# TOBD_STM32.net
KiCad netlist of a schematic drawn in EAGLE
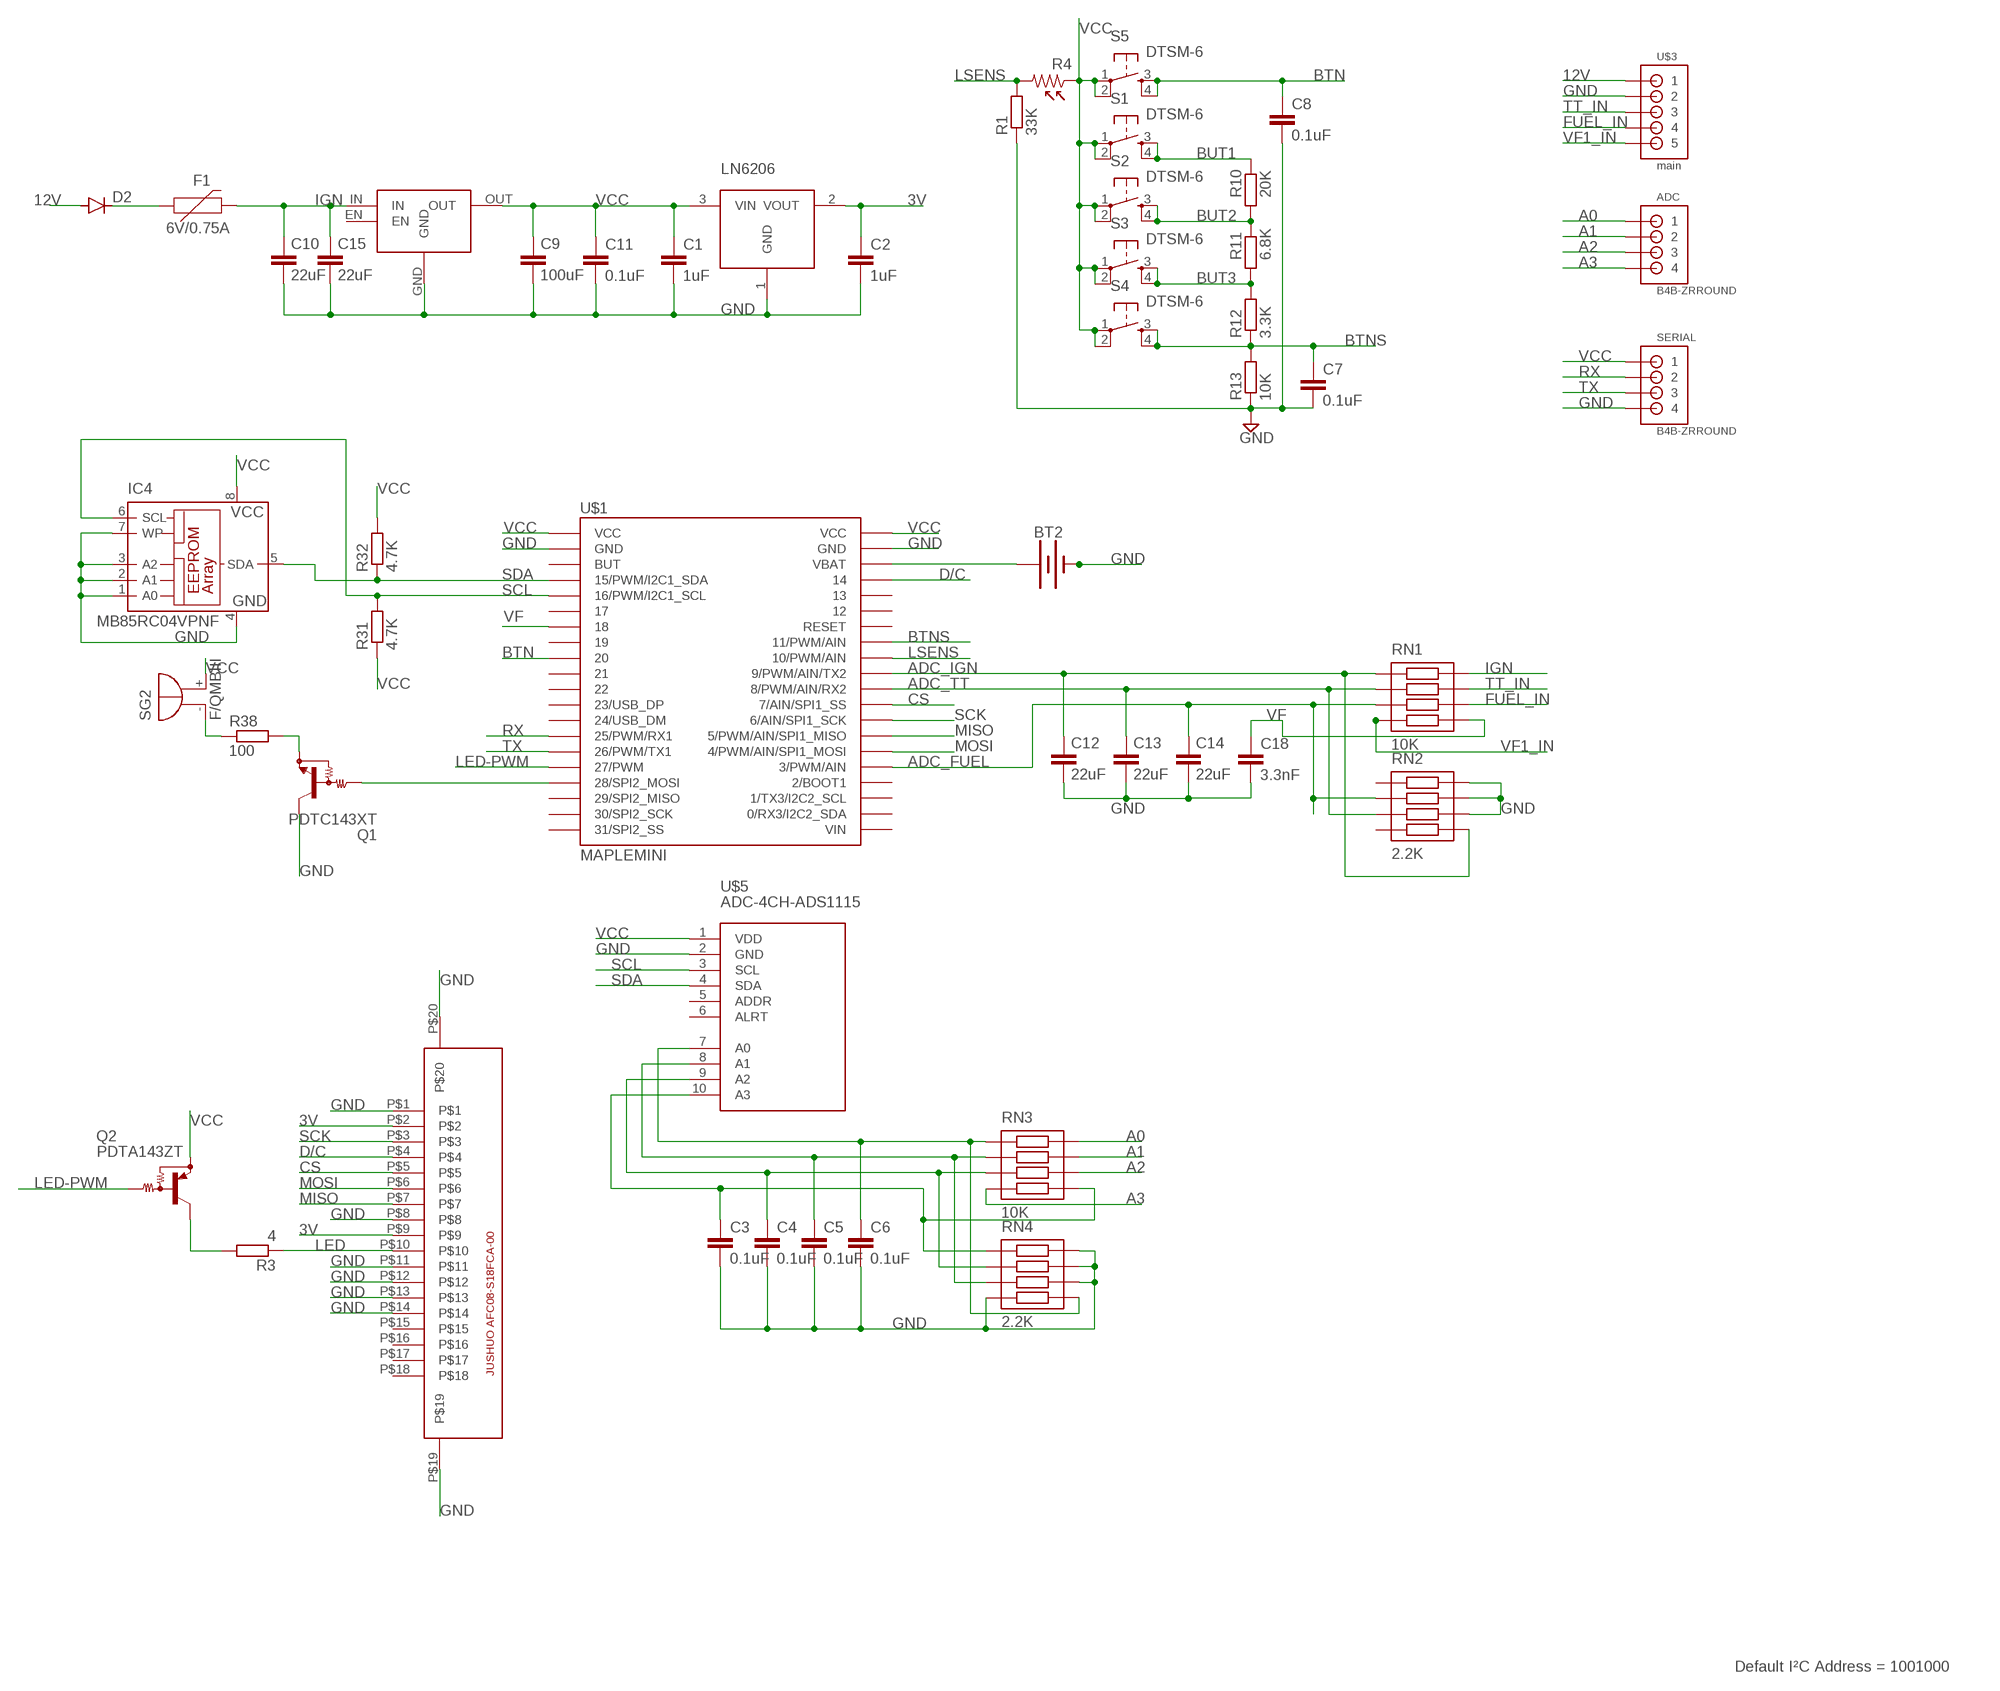
[diagram p0: schematic, sheet 1]

(export (version "E")
  (design (tool "Eeschema 10.0.6"))
  (components
    (comp (ref "ADC")
      (value "B4B-ZRROUND")
      (footprint "eagle-import:B4B-ZR")
      (libsource (lib "eagle-import") (part "B4B-ZRROUND"))
    )
    (comp (ref "BT2")
      (value "BATTERY")
      (footprint "eagle-import:BATTCOM_20MM_VERTICAL")
      (libsource (lib "eagle-import") (part "BATTERY"))
    )
    (comp (ref "C1")
      (value "1uF")
      (footprint "eagle-import:C0805")
      (fields (field (name "MF") "Samsung Electro-Mechanics") (field (name "MPN") "CL21F105ZOFNNNE"))
      (libsource (lib "eagle-import") (part "C-EUC0805"))
    )
    (comp (ref "C2")
      (value "1uF")
      (footprint "eagle-import:C0805")
      (fields (field (name "MF") "Samsung Electro-Mechanics") (field (name "MPN") "CL21F105ZOFNNNE"))
      (libsource (lib "eagle-import") (part "C-EUC0805"))
    )
    (comp (ref "C3")
      (value "0.1uF")
      (footprint "eagle-import:C0805")
      (fields (field (name "MF") "Samsung Electro-Mechanics") (field (name "MPN") "CL21F104ZBCNNNC"))
      (libsource (lib "eagle-import") (part "C-EUC0805"))
    )
    (comp (ref "C4")
      (value "0.1uF")
      (footprint "eagle-import:C0805")
      (fields (field (name "MF") "Samsung Electro-Mechanics") (field (name "MPN") "CL21F104ZBCNNNC"))
      (libsource (lib "eagle-import") (part "C-EUC0805"))
    )
    (comp (ref "C5")
      (value "0.1uF")
      (footprint "eagle-import:C0805")
      (fields (field (name "MF") "Samsung Electro-Mechanics") (field (name "MPN") "CL21F104ZBCNNNC"))
      (libsource (lib "eagle-import") (part "C-EUC0805"))
    )
    (comp (ref "C6")
      (value "0.1uF")
      (footprint "eagle-import:C0805")
      (fields (field (name "MF") "Samsung Electro-Mechanics") (field (name "MPN") "CL21F104ZBCNNNC"))
      (libsource (lib "eagle-import") (part "C-EUC0805"))
    )
    (comp (ref "C7")
      (value "0.1uF")
      (footprint "eagle-import:C0805")
      (fields (field (name "MF") "Samsung Electro-Mechanics") (field (name "MPN") "CL21F104ZBCNNNC"))
      (libsource (lib "eagle-import") (part "C-EUC0805"))
    )
    (comp (ref "C8")
      (value "0.1uF")
      (footprint "eagle-import:C0805")
      (fields (field (name "MF") "Samsung Electro-Mechanics") (field (name "MPN") "CL21F104ZBCNNNC"))
      (libsource (lib "eagle-import") (part "C-EUC0805"))
    )
    (comp (ref "C9")
      (value "100uF")
      (footprint "eagle-import:C1210K")
      (fields (field (name "MF") "Murata Electronics") (field (name "MPN") "GRM32ER60J107ME20L"))
      (libsource (lib "eagle-import") (part "resistor_348_C-EUC1210K"))
    )
    (comp (ref "C10")
      (value "22uF")
      (footprint "eagle-import:C0805")
      (fields (field (name "MF") "Samsung Electro-Mechanics") (field (name "MPN") "CL21A226MAQNNNE"))
      (libsource (lib "eagle-import") (part "resistor_348_C-EUC0805"))
    )
    (comp (ref "C11")
      (value "0.1uF")
      (footprint "eagle-import:C0805")
      (fields (field (name "MF") "Samsung Electro-Mechanics") (field (name "MPN") "CL21F104ZBCNNNC"))
      (libsource (lib "eagle-import") (part "C-EUC0805"))
    )
    (comp (ref "C12")
      (value "22uF")
      (footprint "eagle-import:C0805")
      (fields (field (name "MF") "Samsung Electro-Mechanics") (field (name "MPN") "CL21A226MAQNNNE"))
      (libsource (lib "eagle-import") (part "resistor_348_C-EUC0805"))
    )
    (comp (ref "C13")
      (value "22uF")
      (footprint "eagle-import:C0805")
      (fields (field (name "MF") "Samsung Electro-Mechanics") (field (name "MPN") "CL21A226MAQNNNE"))
      (libsource (lib "eagle-import") (part "resistor_348_C-EUC0805"))
    )
    (comp (ref "C14")
      (value "22uF")
      (footprint "eagle-import:C0805")
      (fields (field (name "MF") "Samsung Electro-Mechanics") (field (name "MPN") "CL21A226MAQNNNE"))
      (libsource (lib "eagle-import") (part "resistor_348_C-EUC0805"))
    )
    (comp (ref "C15")
      (value "22uF")
      (footprint "eagle-import:C0805")
      (fields (field (name "MF") "Samsung Electro-Mechanics") (field (name "MPN") "CL21A226MAQNNNE"))
      (libsource (lib "eagle-import") (part "resistor_348_C-EUC0805"))
    )
    (comp (ref "C18")
      (value "3.3nF")
      (footprint "eagle-import:C0805")
      (fields (field (name "MPN") "CL21B332KBANNNC"))
      (libsource (lib "eagle-import") (part "C-EUC0805"))
    )
    (comp (ref "D2")
      (value "DIODE-DO-214AC")
      (footprint "eagle-import:DO-214AC")
      (libsource (lib "eagle-import") (part "DIODE-DO-214AC"))
    )
    (comp (ref "F1")
      (value "6V/0.75A")
      (footprint "eagle-import:1206")
      (libsource (lib "eagle-import") (part "PPTC_THREE-QUARTER-AMP"))
    )
    (comp (ref "IC4")
      (value "MB85RC04VPNF")
      (footprint "eagle-import:SO-08")
      (libsource (lib "eagle-import") (part "24CSN04A"))
    )
    (comp (ref "LN6206")
      (value "MCP1700")
      (footprint "eagle-import:SOT23")
      (fields (field (name "MPN") "LN6206P302MR-G"))
      (libsource (lib "eagle-import") (part "MCP1700"))
    )
    (comp (ref "Q1")
      (value "PDTC143XT")
      (footprint "eagle-import:SC59-BEC")
      (libsource (lib "eagle-import") (part "MUN2211T1"))
    )
    (comp (ref "Q2")
      (value "PDTA143ZT")
      (footprint "eagle-import:SC59-BEC")
      (libsource (lib "eagle-import") (part "MUN2111T1"))
    )
    (comp (ref "R1")
      (value "33K")
      (footprint "eagle-import:R0805")
      (libsource (lib "eagle-import") (part "R-EU_R0805"))
    )
    (comp (ref "R3")
      (value "4")
      (footprint "eagle-import:R0805")
      (libsource (lib "eagle-import") (part "R-EU_R0805"))
    )
    (comp (ref "R4")
      (value "PHOTORESPDV-P9")
      (footprint "eagle-import:PDV-P9XXX")
      (libsource (lib "eagle-import") (part "PHOTORESPDV-P9"))
    )
    (comp (ref "R10")
      (value "20K")
      (footprint "eagle-import:R0805")
      (libsource (lib "eagle-import") (part "R-EU_R0805"))
    )
    (comp (ref "R11")
      (value "6.8K")
      (footprint "eagle-import:R0805")
      (libsource (lib "eagle-import") (part "R-EU_R0805"))
    )
    (comp (ref "R12")
      (value "3.3K")
      (footprint "eagle-import:R0805")
      (libsource (lib "eagle-import") (part "R-EU_R0805"))
    )
    (comp (ref "R13")
      (value "10K")
      (footprint "eagle-import:R0805")
      (libsource (lib "eagle-import") (part "R-EU_R0805"))
    )
    (comp (ref "R31")
      (value "4.7K")
      (footprint "eagle-import:R0805")
      (libsource (lib "eagle-import") (part "R-EU_R0805"))
    )
    (comp (ref "R32")
      (value "4.7K")
      (footprint "eagle-import:R0805")
      (libsource (lib "eagle-import") (part "R-EU_R0805"))
    )
    (comp (ref "R38")
      (value "100")
      (footprint "eagle-import:R0805")
      (libsource (lib "eagle-import") (part "R-EU_R0805"))
    )
    (comp (ref "RN1")
      (value "10K")
      (footprint "eagle-import:CTS-744_083")
      (fields (field (name "MPN") "CRA064RJ10K0E04Z"))
      (libsource (lib "eagle-import") (part "RN2_EU-4"))
    )
    (comp (ref "RN2")
      (value "2.2K")
      (footprint "eagle-import:CTS-744_083")
      (fields (field (name "MPN") "CRA064RJ10K0E04Z"))
      (libsource (lib "eagle-import") (part "RN2_EU-4"))
    )
    (comp (ref "RN3")
      (value "10K")
      (footprint "eagle-import:CTS-744_083")
      (fields (field (name "MPN") "CRA064RJ10K0E04Z"))
      (libsource (lib "eagle-import") (part "RN2_EU-4"))
    )
    (comp (ref "RN4")
      (value "2.2K")
      (footprint "eagle-import:CTS-744_083")
      (fields (field (name "MPN") "CRA064RJ10K0E04Z"))
      (libsource (lib "eagle-import") (part "RN2_EU-4"))
    )
    (comp (ref "S1")
      (value "DTSM-6")
      (footprint "eagle-import:DTSM-6")
      (libsource (lib "eagle-import") (part "DTSM-6"))
    )
    (comp (ref "S2")
      (value "DTSM-6")
      (footprint "eagle-import:DTSM-6")
      (libsource (lib "eagle-import") (part "DTSM-6"))
    )
    (comp (ref "S3")
      (value "DTSM-6")
      (footprint "eagle-import:DTSM-6")
      (libsource (lib "eagle-import") (part "DTSM-6"))
    )
    (comp (ref "S4")
      (value "DTSM-6")
      (footprint "eagle-import:DTSM-6")
      (libsource (lib "eagle-import") (part "DTSM-6"))
    )
    (comp (ref "S5")
      (value "DTSM-6")
      (footprint "eagle-import:DTSM-6")
      (libsource (lib "eagle-import") (part "DTSM-6"))
    )
    (comp (ref "SERIAL")
      (value "B4B-ZRROUND")
      (footprint "eagle-import:B4B-ZR")
      (libsource (lib "eagle-import") (part "B4B-ZRROUND"))
    )
    (comp (ref "SG2")
      (value "F/QMBIII")
      (footprint "eagle-import:F_QMBIII")
      (libsource (lib "eagle-import") (part "F/QMBIII"))
    )
    (comp (ref "U$1")
      (value "MAPLEMINI")
      (footprint "eagle-import:20-DIP")
      (libsource (lib "eagle-import") (part "MAPLEMINI"))
    )
    (comp (ref "U$2")
      (value "JUSHUOAFC08-S18FCA-00")
      (footprint "eagle-import:JUSHUOAFC08-S18FCA-00")
      (fields (field (name "MPN") "AFC08-S18FCA-00"))
      (libsource (lib "eagle-import") (part "JUSHUOAFC08-S18FCA-00"))
    )
    (comp (ref "U$3")
      (value "main")
      (footprint "eagle-import:B5B-ZR-LONG")
      (libsource (lib "eagle-import") (part "B5B-ZRLONG"))
    )
    (comp (ref "U$4")
      (value "MINI-DC-DC-3AV")
      (footprint "eagle-import:MINI-DC-DC-3AV")
      (libsource (lib "eagle-import") (part "MINI-DC-DC-3AV"))
    )
    (comp (ref "U$5")
      (value "ADC-4CH-ADS1115")
      (footprint "eagle-import:ADC-4CH-ADS1115")
      (libsource (lib "eagle-import") (part "ADC-4CH-ADS1115"))
    )
  )
  (nets
    (net (code "1") (name "/3V") (class "Default")
      (node (ref "C2") (pin "1") (pinfunction "1_1") (pintype "passive"))
      (node (ref "LN6206") (pin "2") (pinfunction "VOUT_2") (pintype "bidirectional"))
      (node (ref "U$2") (pin "P$2") (pinfunction "P$2_P$2") (pintype "bidirectional"))
      (node (ref "U$2") (pin "P$9") (pinfunction "P$9_P$9") (pintype "bidirectional"))
    )
    (net (code "2") (name "/12V") (class "Default")
      (node (ref "D2") (pin "A") (pinfunction "A_A") (pintype "passive"))
      (node (ref "U$3") (pin "1") (pinfunction "1_1") (pintype "bidirectional"))
    )
    (net (code "3") (name "/A0") (class "Default")
      (node (ref "ADC") (pin "1") (pinfunction "1_1") (pintype "bidirectional"))
      (node (ref "RN3") (pin "5") (pinfunction "8_5") (pintype "passive"))
    )
    (net (code "4") (name "/A1") (class "Default")
      (node (ref "ADC") (pin "2") (pinfunction "2_2") (pintype "bidirectional"))
      (node (ref "RN3") (pin "6") (pinfunction "7_6") (pintype "passive"))
    )
    (net (code "5") (name "/A2") (class "Default")
      (node (ref "ADC") (pin "3") (pinfunction "3_3") (pintype "bidirectional"))
      (node (ref "RN3") (pin "7") (pinfunction "6_7") (pintype "passive"))
    )
    (net (code "6") (name "/A3") (class "Default")
      (node (ref "ADC") (pin "4") (pinfunction "4_4") (pintype "bidirectional"))
      (node (ref "RN3") (pin "8") (pinfunction "4_8") (pintype "passive"))
    )
    (net (code "7") (name "/ADC_FUEL") (class "Default")
      (node (ref "C14") (pin "1") (pinfunction "1_1") (pintype "passive"))
      (node (ref "RN1") (pin "2") (pinfunction "3_2") (pintype "passive"))
      (node (ref "RN2") (pin "3") (pinfunction "2_3") (pintype "passive"))
      (node (ref "U$1") (pin "25") (pinfunction "3/PWM/AIN_25") (pintype "bidirectional"))
    )
    (net (code "8") (name "/ADC_IGN") (class "Default")
      (node (ref "C12") (pin "1") (pinfunction "1_1") (pintype "passive"))
      (node (ref "RN1") (pin "4") (pinfunction "1_4") (pintype "passive"))
      (node (ref "RN2") (pin "1") (pinfunction "5_1") (pintype "passive"))
      (node (ref "U$1") (pin "31") (pinfunction "9/PWM/AIN/TX2_31") (pintype "bidirectional"))
    )
    (net (code "9") (name "/ADC_TT") (class "Default")
      (node (ref "C13") (pin "1") (pinfunction "1_1") (pintype "passive"))
      (node (ref "RN1") (pin "3") (pinfunction "2_3") (pintype "passive"))
      (node (ref "RN2") (pin "2") (pinfunction "3_2") (pintype "passive"))
      (node (ref "U$1") (pin "30") (pinfunction "8/PWM/AIN/RX2_30") (pintype "bidirectional"))
    )
    (net (code "10") (name "/BTN") (class "Default")
      (node (ref "C8") (pin "1") (pinfunction "1_1") (pintype "passive"))
      (node (ref "S5") (pin "3") (pinfunction "3_3") (pintype "passive"))
      (node (ref "S5") (pin "4") (pinfunction "4_4") (pintype "passive"))
      (node (ref "U$1") (pin "9") (pinfunction "20_9") (pintype "bidirectional"))
    )
    (net (code "11") (name "/BTNS") (class "Default")
      (node (ref "C7") (pin "1") (pinfunction "1_1") (pintype "passive"))
      (node (ref "R12") (pin "1") (pinfunction "1_1") (pintype "passive"))
      (node (ref "R13") (pin "2") (pinfunction "2_2") (pintype "passive"))
      (node (ref "S4") (pin "3") (pinfunction "3_3") (pintype "passive"))
      (node (ref "S4") (pin "4") (pinfunction "4_4") (pintype "passive"))
      (node (ref "U$1") (pin "33") (pinfunction "11/PWM/AIN_33") (pintype "bidirectional"))
    )
    (net (code "12") (name "/BUT1") (class "Default")
      (node (ref "R10") (pin "2") (pinfunction "2_2") (pintype "passive"))
      (node (ref "S1") (pin "3") (pinfunction "3_3") (pintype "passive"))
      (node (ref "S1") (pin "4") (pinfunction "4_4") (pintype "passive"))
    )
    (net (code "13") (name "/BUT2") (class "Default")
      (node (ref "R10") (pin "1") (pinfunction "1_1") (pintype "passive"))
      (node (ref "R11") (pin "2") (pinfunction "2_2") (pintype "passive"))
      (node (ref "S2") (pin "3") (pinfunction "3_3") (pintype "passive"))
      (node (ref "S2") (pin "4") (pinfunction "4_4") (pintype "passive"))
    )
    (net (code "14") (name "/BUT3") (class "Default")
      (node (ref "R11") (pin "1") (pinfunction "1_1") (pintype "passive"))
      (node (ref "R12") (pin "2") (pinfunction "2_2") (pintype "passive"))
      (node (ref "S3") (pin "3") (pinfunction "3_3") (pintype "passive"))
      (node (ref "S3") (pin "4") (pinfunction "4_4") (pintype "passive"))
    )
    (net (code "15") (name "/CS") (class "Default")
      (node (ref "U$1") (pin "29") (pinfunction "7/AIN/SPI1_SS_29") (pintype "bidirectional"))
      (node (ref "U$2") (pin "P$5") (pinfunction "P$5_P$5") (pintype "bidirectional"))
    )
    (net (code "16") (name "/D{slash}C") (class "Default")
      (node (ref "U$1") (pin "37") (pinfunction "14_37") (pintype "bidirectional"))
      (node (ref "U$2") (pin "P$4") (pinfunction "P$4_P$4") (pintype "bidirectional"))
    )
    (net (code "17") (name "/FUEL_IN") (class "Default")
      (node (ref "RN1") (pin "7") (pinfunction "6_7") (pintype "passive"))
      (node (ref "U$3") (pin "4") (pinfunction "4_4") (pintype "bidirectional"))
    )
    (net (code "18") (name "/IGN") (class "Default")
      (node (ref "C10") (pin "1") (pinfunction "1_1") (pintype "passive"))
      (node (ref "C15") (pin "1") (pinfunction "1_1") (pintype "passive"))
      (node (ref "F1") (pin "2") (pinfunction "2_2") (pintype "bidirectional"))
      (node (ref "RN1") (pin "5") (pinfunction "8_5") (pintype "passive"))
      (node (ref "U$4") (pin "IN") (pinfunction "IN_IN") (pintype "bidirectional"))
    )
    (net (code "19") (name "/LED") (class "Default")
      (node (ref "R3") (pin "1") (pinfunction "1_1") (pintype "passive"))
      (node (ref "U$2") (pin "P$10") (pinfunction "P$10_P$10") (pintype "bidirectional"))
    )
    (net (code "20") (name "/LED-PWM") (class "Default")
      (node (ref "Q2") (pin "B") (pinfunction "B_B") (pintype "passive"))
      (node (ref "U$1") (pin "16") (pinfunction "27/PWM_16") (pintype "bidirectional"))
    )
    (net (code "21") (name "/LSENS") (class "Default")
      (node (ref "R1") (pin "2") (pinfunction "2_2") (pintype "passive"))
      (node (ref "R4") (pin "2") (pinfunction "2_2") (pintype "passive"))
      (node (ref "U$1") (pin "32") (pinfunction "10/PWM/AIN_32") (pintype "bidirectional"))
    )
    (net (code "22") (name "/MISO") (class "Default")
      (node (ref "U$1") (pin "27") (pinfunction "5/PWM/AIN/SPI1_MISO_27") (pintype "bidirectional"))
      (node (ref "U$2") (pin "P$7") (pinfunction "P$7_P$7") (pintype "bidirectional"))
    )
    (net (code "23") (name "/MOSI") (class "Default")
      (node (ref "U$1") (pin "26") (pinfunction "4/PWM/AIN/SPI1_MOSI_26") (pintype "bidirectional"))
      (node (ref "U$2") (pin "P$6") (pinfunction "P$6_P$6") (pintype "bidirectional"))
    )
    (net (code "24") (name "/RX") (class "Default")
      (node (ref "SERIAL") (pin "2") (pinfunction "2_2") (pintype "bidirectional"))
      (node (ref "U$1") (pin "14") (pinfunction "25/PWM/RX1_14") (pintype "bidirectional"))
    )
    (net (code "25") (name "/SCK") (class "Default")
      (node (ref "U$1") (pin "28") (pinfunction "6/AIN/SPI1_SCK_28") (pintype "bidirectional"))
      (node (ref "U$2") (pin "P$3") (pinfunction "P$3_P$3") (pintype "bidirectional"))
    )
    (net (code "26") (name "/SCL") (class "Default")
      (node (ref "IC4") (pin "6") (pinfunction "SCL_6") (pintype "input"))
      (node (ref "R31") (pin "2") (pinfunction "2_2") (pintype "passive"))
      (node (ref "U$1") (pin "5") (pinfunction "16/PWM/I2C1_SCL_5") (pintype "bidirectional"))
      (node (ref "U$5") (pin "3") (pinfunction "SCL_3") (pintype "bidirectional"))
    )
    (net (code "27") (name "/SDA") (class "Default")
      (node (ref "IC4") (pin "5") (pinfunction "SDA_5") (pintype "bidirectional"))
      (node (ref "R32") (pin "1") (pinfunction "1_1") (pintype "passive"))
      (node (ref "U$1") (pin "4") (pinfunction "15/PWM/I2C1_SDA_4") (pintype "bidirectional"))
      (node (ref "U$5") (pin "4") (pinfunction "SDA_4") (pintype "bidirectional"))
    )
    (net (code "28") (name "/TT_IN") (class "Default")
      (node (ref "RN1") (pin "6") (pinfunction "7_6") (pintype "passive"))
      (node (ref "U$3") (pin "3") (pinfunction "3_3") (pintype "bidirectional"))
    )
    (net (code "29") (name "/TX") (class "Default")
      (node (ref "SERIAL") (pin "3") (pinfunction "3_3") (pintype "bidirectional"))
      (node (ref "U$1") (pin "15") (pinfunction "26/PWM/TX1_15") (pintype "bidirectional"))
    )
    (net (code "30") (name "/VCC") (class "Default")
      (node (ref "C1") (pin "1") (pinfunction "1_1") (pintype "passive"))
      (node (ref "C11") (pin "1") (pinfunction "1_1") (pintype "passive"))
      (node (ref "C9") (pin "1") (pinfunction "1_1") (pintype "passive"))
      (node (ref "IC4") (pin "8") (pinfunction "VCC_8") (pintype "power_in"))
      (node (ref "LN6206") (pin "3") (pinfunction "VIN_3") (pintype "bidirectional"))
      (node (ref "Q2") (pin "E") (pinfunction "E_E") (pintype "passive"))
      (node (ref "R31") (pin "1") (pinfunction "1_1") (pintype "passive"))
      (node (ref "R32") (pin "2") (pinfunction "2_2") (pintype "passive"))
      (node (ref "R4") (pin "1") (pinfunction "1_1") (pintype "passive"))
      (node (ref "S1") (pin "1") (pinfunction "1_1") (pintype "passive"))
      (node (ref "S1") (pin "2") (pinfunction "2_2") (pintype "passive"))
      (node (ref "S2") (pin "1") (pinfunction "1_1") (pintype "passive"))
      (node (ref "S2") (pin "2") (pinfunction "2_2") (pintype "passive"))
      (node (ref "S3") (pin "1") (pinfunction "1_1") (pintype "passive"))
      (node (ref "S3") (pin "2") (pinfunction "2_2") (pintype "passive"))
      (node (ref "S4") (pin "1") (pinfunction "1_1") (pintype "passive"))
      (node (ref "S4") (pin "2") (pinfunction "2_2") (pintype "passive"))
      (node (ref "S5") (pin "1") (pinfunction "1_1") (pintype "passive"))
      (node (ref "S5") (pin "2") (pinfunction "2_2") (pintype "passive"))
      (node (ref "SERIAL") (pin "1") (pinfunction "1_1") (pintype "bidirectional"))
      (node (ref "SG2") (pin "+") (pinfunction "-_+") (pintype "passive"))
      (node (ref "U$1") (pin "1") (pinfunction "VCC_1") (pintype "bidirectional"))
      (node (ref "U$1") (pin "40") (pinfunction "VCC_40") (pintype "bidirectional"))
      (node (ref "U$4") (pin "OUT") (pinfunction "OUT_OUT") (pintype "bidirectional"))
      (node (ref "U$5") (pin "1") (pinfunction "VDD_1") (pintype "power_in"))
    )
    (net (code "31") (name "/VF") (class "Default")
      (node (ref "C18") (pin "1") (pinfunction "1_1") (pintype "passive"))
      (node (ref "RN1") (pin "1") (pinfunction "5_1") (pintype "passive"))
      (node (ref "U$1") (pin "7") (pinfunction "18_7") (pintype "bidirectional"))
    )
    (net (code "32") (name "/VF1_IN") (class "Default")
      (node (ref "RN1") (pin "8") (pinfunction "4_8") (pintype "passive"))
      (node (ref "U$3") (pin "5") (pinfunction "5_5") (pintype "bidirectional"))
    )
    (net (code "33") (name "GND") (class "Default")
      (node (ref "BT2") (pin "3") (pinfunction "-_3") (pintype "power_in"))
      (node (ref "C1") (pin "2") (pinfunction "2_2") (pintype "passive"))
      (node (ref "C10") (pin "2") (pinfunction "2_2") (pintype "passive"))
      (node (ref "C11") (pin "2") (pinfunction "2_2") (pintype "passive"))
      (node (ref "C12") (pin "2") (pinfunction "2_2") (pintype "passive"))
      (node (ref "C13") (pin "2") (pinfunction "2_2") (pintype "passive"))
      (node (ref "C14") (pin "2") (pinfunction "2_2") (pintype "passive"))
      (node (ref "C15") (pin "2") (pinfunction "2_2") (pintype "passive"))
      (node (ref "C18") (pin "2") (pinfunction "2_2") (pintype "passive"))
      (node (ref "C2") (pin "2") (pinfunction "2_2") (pintype "passive"))
      (node (ref "C3") (pin "2") (pinfunction "2_2") (pintype "passive"))
      (node (ref "C4") (pin "2") (pinfunction "2_2") (pintype "passive"))
      (node (ref "C5") (pin "2") (pinfunction "2_2") (pintype "passive"))
      (node (ref "C6") (pin "2") (pinfunction "2_2") (pintype "passive"))
      (node (ref "C7") (pin "2") (pinfunction "2_2") (pintype "passive"))
      (node (ref "C8") (pin "2") (pinfunction "2_2") (pintype "passive"))
      (node (ref "C9") (pin "2") (pinfunction "2_2") (pintype "passive"))
      (node (ref "IC4") (pin "1") (pinfunction "A0_1") (pintype "input"))
      (node (ref "IC4") (pin "2") (pinfunction "A1_2") (pintype "input"))
      (node (ref "IC4") (pin "3") (pinfunction "A2_3") (pintype "input"))
      (node (ref "IC4") (pin "4") (pinfunction "GND_4") (pintype "power_in"))
      (node (ref "IC4") (pin "7") (pinfunction "WP_7") (pintype "input"))
      (node (ref "LN6206") (pin "1") (pinfunction "GND_1") (pintype "bidirectional"))
      (node (ref "Q1") (pin "C") (pinfunction "C_C") (pintype "passive"))
      (node (ref "R1") (pin "1") (pinfunction "1_1") (pintype "passive"))
      (node (ref "R13") (pin "1") (pinfunction "1_1") (pintype "passive"))
      (node (ref "RN2") (pin "5") (pinfunction "8_5") (pintype "passive"))
      (node (ref "RN2") (pin "6") (pinfunction "7_6") (pintype "passive"))
      (node (ref "RN2") (pin "7") (pinfunction "6_7") (pintype "passive"))
      (node (ref "RN4") (pin "5") (pinfunction "8_5") (pintype "passive"))
      (node (ref "RN4") (pin "6") (pinfunction "7_6") (pintype "passive"))
      (node (ref "RN4") (pin "7") (pinfunction "6_7") (pintype "passive"))
      (node (ref "RN4") (pin "8") (pinfunction "4_8") (pintype "passive"))
      (node (ref "SERIAL") (pin "4") (pinfunction "4_4") (pintype "bidirectional"))
      (node (ref "U$1") (pin "2") (pinfunction "GND_2") (pintype "bidirectional"))
      (node (ref "U$1") (pin "39") (pinfunction "GND_39") (pintype "bidirectional"))
      (node (ref "U$2") (pin "P$1") (pinfunction "P$1_P$1") (pintype "bidirectional"))
      (node (ref "U$2") (pin "P$11") (pinfunction "P$11_P$11") (pintype "bidirectional"))
      (node (ref "U$2") (pin "P$12") (pinfunction "P$12_P$12") (pintype "bidirectional"))
      (node (ref "U$2") (pin "P$13") (pinfunction "P$13_P$13") (pintype "bidirectional"))
      (node (ref "U$2") (pin "P$14") (pinfunction "P$14_P$14") (pintype "bidirectional"))
      (node (ref "U$2") (pin "P$19") (pinfunction "P$19_P$19") (pintype "bidirectional"))
      (node (ref "U$2") (pin "P$20") (pinfunction "P$20_P$20") (pintype "bidirectional"))
      (node (ref "U$2") (pin "P$8") (pinfunction "P$8_P$8") (pintype "bidirectional"))
      (node (ref "U$3") (pin "2") (pinfunction "2_2") (pintype "bidirectional"))
      (node (ref "U$4") (pin "GND") (pinfunction "GND_GND") (pintype "bidirectional"))
      (node (ref "U$5") (pin "2") (pinfunction "GND_2") (pintype "power_in"))
    )
    (net (code "34") (name "Net-(D2-PadC)") (class "Default")
      (node (ref "D2") (pin "C") (pinfunction "C_C") (pintype "passive"))
      (node (ref "F1") (pin "1") (pinfunction "1_1") (pintype "bidirectional"))
    )
    (net (code "35") (name "Net-(Q1-PadE)") (class "Default")
      (node (ref "Q1") (pin "E") (pinfunction "E_E") (pintype "passive"))
      (node (ref "R38") (pin "2") (pinfunction "2_2") (pintype "passive"))
    )
    (net (code "36") (name "Net-(Q2-PadC)") (class "Default")
      (node (ref "Q2") (pin "C") (pinfunction "C_C") (pintype "passive"))
      (node (ref "R3") (pin "2") (pinfunction "2_2") (pintype "passive"))
    )
    (net (code "37") (name "Net-(RN3-1)") (class "Default")
      (node (ref "C6") (pin "1") (pinfunction "1_1") (pintype "passive"))
      (node (ref "RN3") (pin "4") (pinfunction "1_4") (pintype "passive"))
      (node (ref "RN4") (pin "1") (pinfunction "5_1") (pintype "passive"))
      (node (ref "U$5") (pin "7") (pinfunction "A0_7") (pintype "input"))
    )
    (net (code "38") (name "Net-(RN3-2)") (class "Default")
      (node (ref "C5") (pin "1") (pinfunction "1_1") (pintype "passive"))
      (node (ref "RN3") (pin "3") (pinfunction "2_3") (pintype "passive"))
      (node (ref "RN4") (pin "2") (pinfunction "3_2") (pintype "passive"))
      (node (ref "U$5") (pin "8") (pinfunction "A1_8") (pintype "input"))
    )
    (net (code "39") (name "Net-(RN3-3)") (class "Default")
      (node (ref "C4") (pin "1") (pinfunction "1_1") (pintype "passive"))
      (node (ref "RN3") (pin "2") (pinfunction "3_2") (pintype "passive"))
      (node (ref "RN4") (pin "3") (pinfunction "2_3") (pintype "passive"))
      (node (ref "U$5") (pin "9") (pinfunction "A2_9") (pintype "input"))
    )
    (net (code "40") (name "Net-(RN3-5)") (class "Default")
      (node (ref "C3") (pin "1") (pinfunction "1_1") (pintype "passive"))
      (node (ref "RN3") (pin "1") (pinfunction "5_1") (pintype "passive"))
      (node (ref "RN4") (pin "4") (pinfunction "1_4") (pintype "passive"))
      (node (ref "U$5") (pin "10") (pinfunction "A3_10") (pintype "input"))
    )
    (net (code "41") (name "Net-(SG2-+)") (class "Default")
      (node (ref "R38") (pin "1") (pinfunction "1_1") (pintype "passive"))
      (node (ref "SG2") (pin "-") (pinfunction "+_-") (pintype "passive"))
    )
    (net (code "42") (name "Net-(U$1-28{slash}SPI2_MOSI)") (class "Default")
      (node (ref "Q1") (pin "B") (pinfunction "B_B") (pintype "passive"))
      (node (ref "U$1") (pin "17") (pinfunction "28/SPI2_MOSI_17") (pintype "bidirectional"))
    )
    (net (code "43") (name "Net-(U$1-VBAT)") (class "Default")
      (node (ref "BT2") (pin "1") (pinfunction "+_1") (pintype "power_in"))
      (node (ref "BT2") (pin "2") (pinfunction "+_2") (pintype "power_in"))
      (node (ref "U$1") (pin "38") (pinfunction "VBAT_38") (pintype "bidirectional"))
    )
    (net (code "44") (name "unconnected-(RN2-1-Pad4)") (class "Default")
      (node (ref "RN2") (pin "4") (pinfunction "1_4") (pintype "passive"))
    )
    (net (code "45") (name "unconnected-(RN2-4-Pad8)") (class "Default")
      (node (ref "RN2") (pin "8") (pinfunction "4_8") (pintype "passive"))
    )
    (net (code "46") (name "unconnected-(U$1-0{slash}RX3{slash}I2C2_SDA-Pad22)") (class "Default")
      (node (ref "U$1") (pin "22") (pinfunction "0/RX3/I2C2_SDA_22") (pintype "bidirectional"))
    )
    (net (code "47") (name "unconnected-(U$1-1{slash}TX3{slash}I2C2_SCL-Pad23)") (class "Default")
      (node (ref "U$1") (pin "23") (pinfunction "1/TX3/I2C2_SCL_23") (pintype "bidirectional"))
    )
    (net (code "48") (name "unconnected-(U$1-2{slash}BOOT1-Pad24)") (class "Default")
      (node (ref "U$1") (pin "24") (pinfunction "2/BOOT1_24") (pintype "bidirectional"))
    )
    (net (code "49") (name "unconnected-(U$1-12-Pad35)") (class "Default")
      (node (ref "U$1") (pin "35") (pinfunction "12_35") (pintype "bidirectional"))
    )
    (net (code "50") (name "unconnected-(U$1-13-Pad36)") (class "Default")
      (node (ref "U$1") (pin "36") (pinfunction "13_36") (pintype "bidirectional"))
    )
    (net (code "51") (name "unconnected-(U$1-17-Pad6)") (class "Default")
      (node (ref "U$1") (pin "6") (pinfunction "17_6") (pintype "bidirectional"))
    )
    (net (code "52") (name "unconnected-(U$1-19-Pad8)") (class "Default")
      (node (ref "U$1") (pin "8") (pinfunction "19_8") (pintype "bidirectional"))
    )
    (net (code "53") (name "unconnected-(U$1-21-Pad10)") (class "Default")
      (node (ref "U$1") (pin "10") (pinfunction "21_10") (pintype "bidirectional"))
    )
    (net (code "54") (name "unconnected-(U$1-22-Pad11)") (class "Default")
      (node (ref "U$1") (pin "11") (pinfunction "22_11") (pintype "bidirectional"))
    )
    (net (code "55") (name "unconnected-(U$1-23{slash}USB_DP-Pad12)") (class "Default")
      (node (ref "U$1") (pin "12") (pinfunction "23/USB_DP_12") (pintype "bidirectional"))
    )
    (net (code "56") (name "unconnected-(U$1-24{slash}USB_DM-Pad13)") (class "Default")
      (node (ref "U$1") (pin "13") (pinfunction "24/USB_DM_13") (pintype "bidirectional"))
    )
    (net (code "57") (name "unconnected-(U$1-29{slash}SPI2_MISO-Pad18)") (class "Default")
      (node (ref "U$1") (pin "18") (pinfunction "29/SPI2_MISO_18") (pintype "bidirectional"))
    )
    (net (code "58") (name "unconnected-(U$1-30{slash}SPI2_SCK-Pad19)") (class "Default")
      (node (ref "U$1") (pin "19") (pinfunction "30/SPI2_SCK_19") (pintype "bidirectional"))
    )
    (net (code "59") (name "unconnected-(U$1-31{slash}SPI2_SS-Pad20)") (class "Default")
      (node (ref "U$1") (pin "20") (pinfunction "31/SPI2_SS_20") (pintype "bidirectional"))
    )
    (net (code "60") (name "unconnected-(U$1-BUT-Pad3)") (class "Default")
      (node (ref "U$1") (pin "3") (pinfunction "BUT_3") (pintype "bidirectional"))
    )
    (net (code "61") (name "unconnected-(U$1-RESET-Pad34)") (class "Default")
      (node (ref "U$1") (pin "34") (pinfunction "RESET_34") (pintype "bidirectional"))
    )
    (net (code "62") (name "unconnected-(U$1-VIN-Pad21)") (class "Default")
      (node (ref "U$1") (pin "21") (pinfunction "VIN_21") (pintype "bidirectional"))
    )
    (net (code "63") (name "unconnected-(U$2-PadP$15)") (class "Default")
      (node (ref "U$2") (pin "P$15") (pinfunction "P$15_P$15") (pintype "bidirectional"))
    )
    (net (code "64") (name "unconnected-(U$2-PadP$16)") (class "Default")
      (node (ref "U$2") (pin "P$16") (pinfunction "P$16_P$16") (pintype "bidirectional"))
    )
    (net (code "65") (name "unconnected-(U$2-PadP$17)") (class "Default")
      (node (ref "U$2") (pin "P$17") (pinfunction "P$17_P$17") (pintype "bidirectional"))
    )
    (net (code "66") (name "unconnected-(U$2-PadP$18)") (class "Default")
      (node (ref "U$2") (pin "P$18") (pinfunction "P$18_P$18") (pintype "bidirectional"))
    )
    (net (code "67") (name "unconnected-(U$4-PadEN)") (class "Default")
      (node (ref "U$4") (pin "EN") (pinfunction "EN_EN") (pintype "bidirectional"))
    )
    (net (code "68") (name "unconnected-(U$5-ADDR-Pad5)") (class "Default")
      (node (ref "U$5") (pin "5") (pinfunction "ADDR_5") (pintype "bidirectional"))
    )
    (net (code "69") (name "unconnected-(U$5-ALRT-Pad6)") (class "Default")
      (node (ref "U$5") (pin "6") (pinfunction "ALRT_6") (pintype "bidirectional"))
    )
  )
)
